# MicroController.net
KiCad netlist of a schematic drawn in Altium Designer
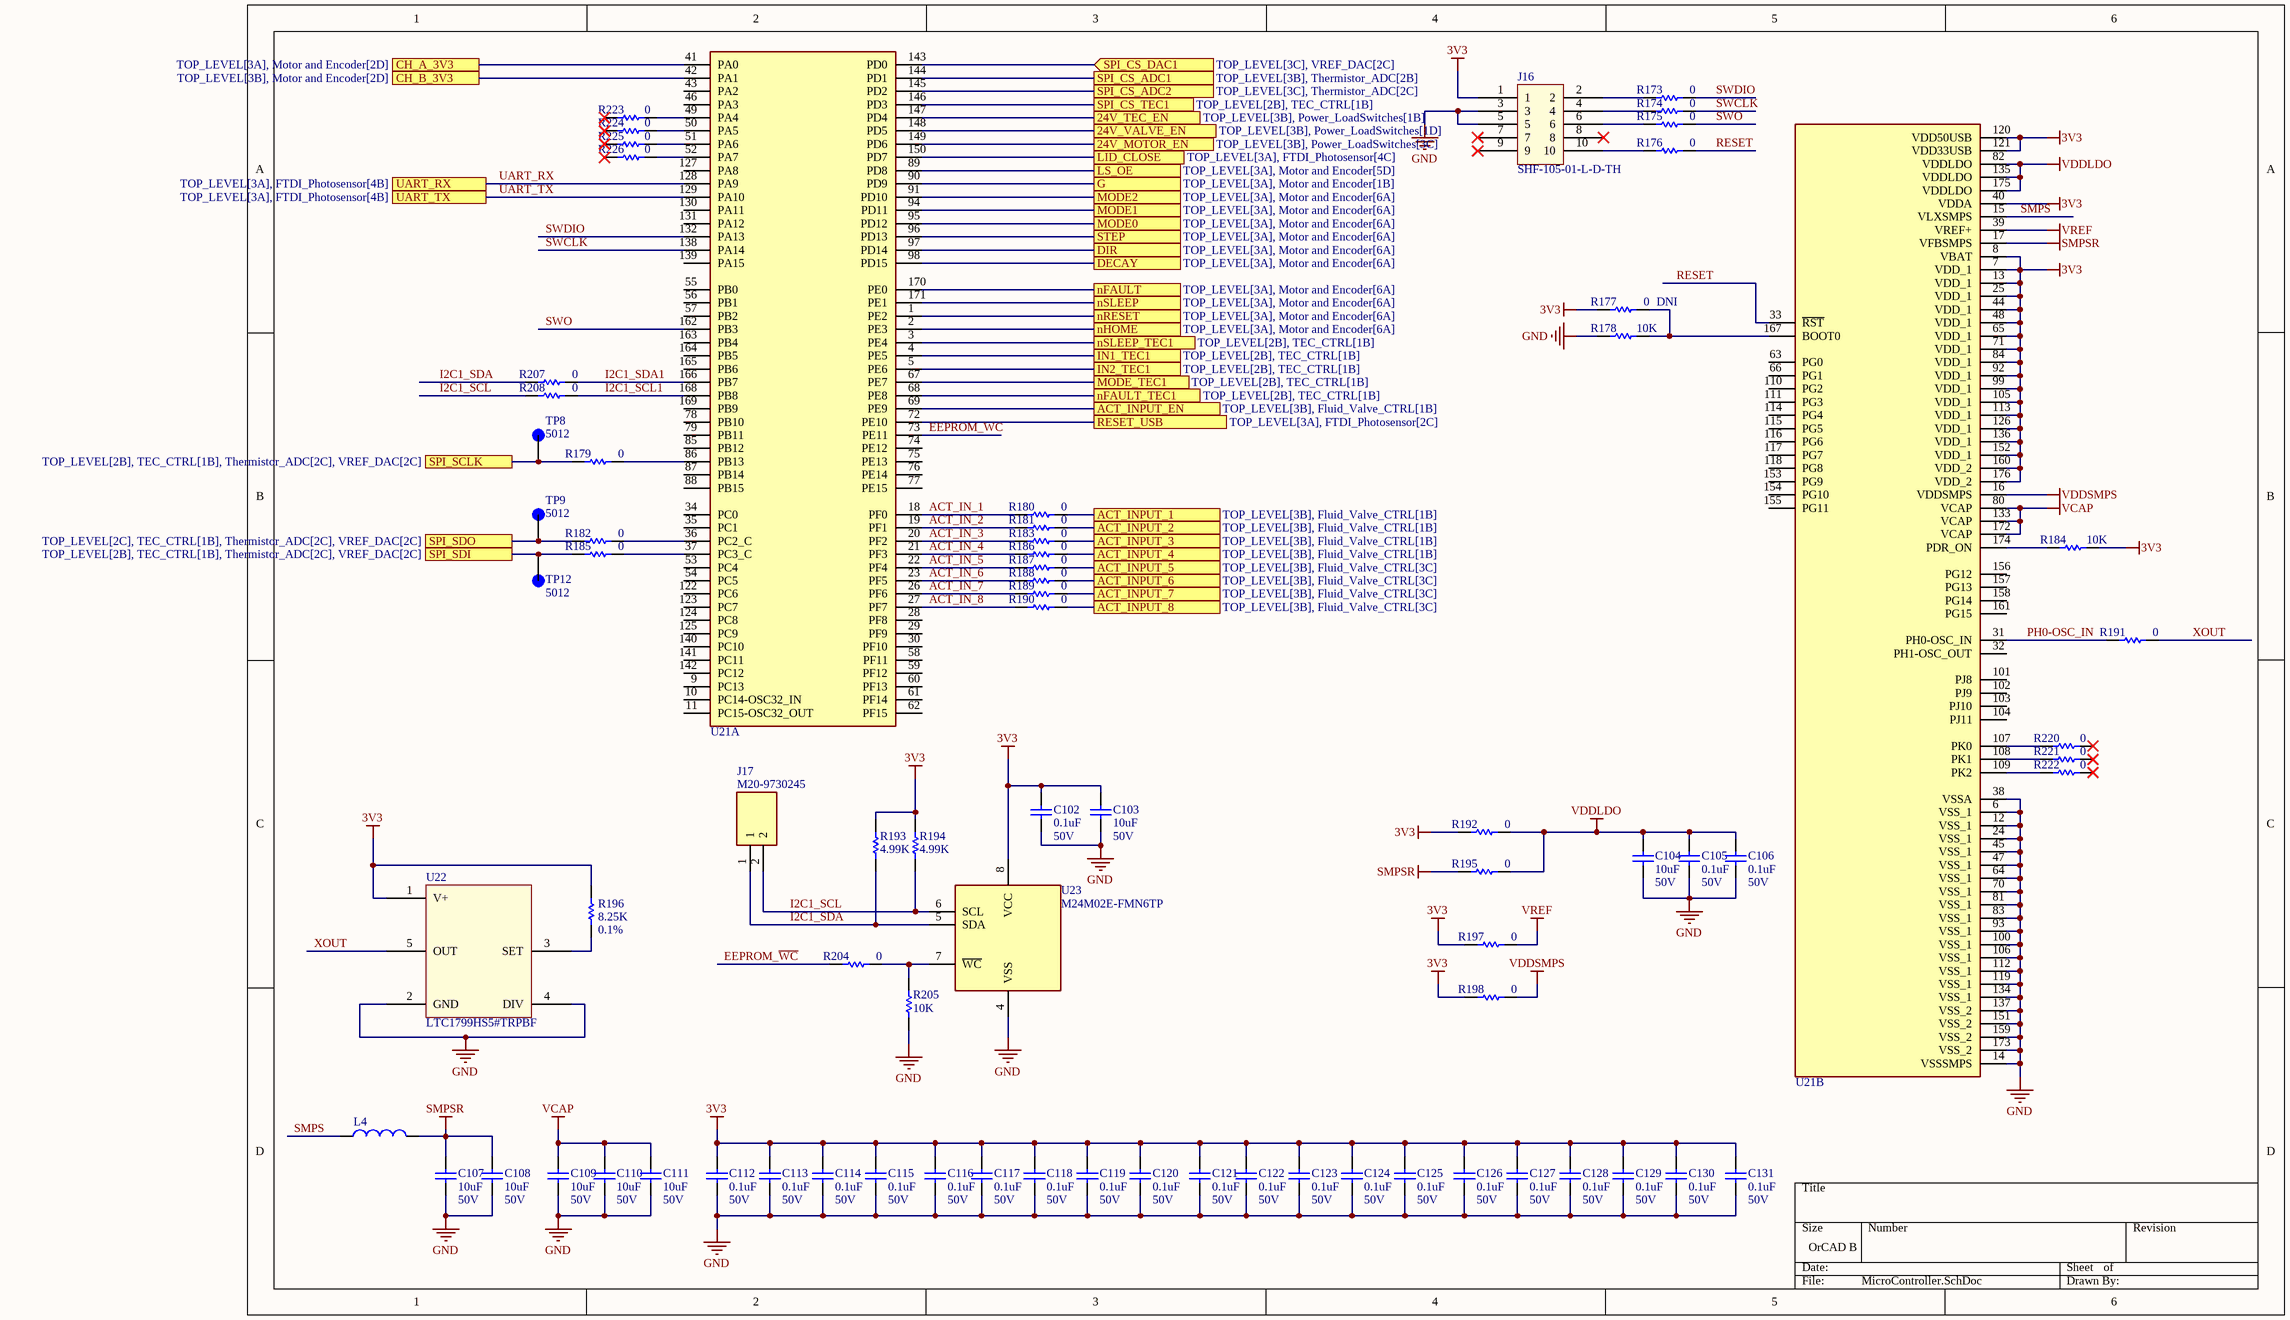
[diagram p0: MicroController.SchDoc]

(export (version "E")
  (design (tool "Eeschema 10.0.6"))
  (components
    (comp (ref "C102")
      (value "0.1uF")
      (footprint "DEFAULT_CAPACITOR_0805")
      (description "CAP CER 0.1UF 50V X7R 0805")
      (fields
        (field (name "MANUFACTURER") "Cal-Chip Electronics, Inc.")
        (field (name "RATING") "50V")
        (field (name "Comment") "KGM21NR71H104KT")
      )
      (libsource (lib "Avery Altium Llibrary") (part "KGM21NR71H104KT"))
    )
    (comp (ref "C103")
      (value "10uF")
      (footprint "DEFAULT_CAPACITOR_0805")
      (description "CAP CER 10UF 50V X5R 0805")
      (fields (field (name "RATING") "50V") (field (name "Comment") "GRM21BR61H106KE43L"))
      (libsource (lib "Avery Altium Llibrary") (part "GRM21BR61H106KE43L"))
    )
    (comp (ref "C104")
      (value "10uF")
      (footprint "DEFAULT_CAPACITOR_0805")
      (description "CAP CER 10UF 50V X5R 0805")
      (fields (field (name "RATING") "50V") (field (name "Comment") "GRM21BR61H106KE43L"))
      (libsource (lib "Avery Altium Llibrary") (part "GRM21BR61H106KE43L"))
    )
    (comp (ref "C105")
      (value "0.1uF")
      (footprint "DEFAULT_CAPACITOR_0805")
      (description "CAP CER 0.1UF 50V X7R 0805")
      (fields
        (field (name "MANUFACTURER") "Cal-Chip Electronics, Inc.")
        (field (name "RATING") "50V")
        (field (name "Comment") "KGM21NR71H104KT")
      )
      (libsource (lib "Avery Altium Llibrary") (part "KGM21NR71H104KT"))
    )
    (comp (ref "C106")
      (value "0.1uF")
      (footprint "DEFAULT_CAPACITOR_0805")
      (description "CAP CER 0.1UF 50V X7R 0805")
      (fields
        (field (name "MANUFACTURER") "Cal-Chip Electronics, Inc.")
        (field (name "RATING") "50V")
        (field (name "Comment") "KGM21NR71H104KT")
      )
      (libsource (lib "Avery Altium Llibrary") (part "KGM21NR71H104KT"))
    )
    (comp (ref "C107")
      (value "10uF")
      (footprint "DEFAULT_CAPACITOR_0805")
      (description "CAP CER 10UF 50V X5R 0805")
      (fields (field (name "RATING") "50V") (field (name "Comment") "GRM21BR61H106KE43L"))
      (libsource (lib "Avery Altium Llibrary") (part "GRM21BR61H106KE43L"))
    )
    (comp (ref "C108")
      (value "10uF")
      (footprint "DEFAULT_CAPACITOR_0805")
      (description "CAP CER 10UF 50V X5R 0805")
      (fields (field (name "RATING") "50V") (field (name "Comment") "GRM21BR61H106KE43L"))
      (libsource (lib "Avery Altium Llibrary") (part "GRM21BR61H106KE43L"))
    )
    (comp (ref "C109")
      (value "10uF")
      (footprint "DEFAULT_CAPACITOR_0805")
      (description "CAP CER 10UF 50V X5R 0805")
      (fields (field (name "RATING") "50V") (field (name "Comment") "GRM21BR61H106KE43L"))
      (libsource (lib "Avery Altium Llibrary") (part "GRM21BR61H106KE43L"))
    )
    (comp (ref "C110")
      (value "10uF")
      (footprint "DEFAULT_CAPACITOR_0805")
      (description "CAP CER 10UF 50V X5R 0805")
      (fields (field (name "RATING") "50V") (field (name "Comment") "GRM21BR61H106KE43L"))
      (libsource (lib "Avery Altium Llibrary") (part "GRM21BR61H106KE43L"))
    )
    (comp (ref "C111")
      (value "10uF")
      (footprint "DEFAULT_CAPACITOR_0805")
      (description "CAP CER 10UF 50V X5R 0805")
      (fields (field (name "RATING") "50V") (field (name "Comment") "GRM21BR61H106KE43L"))
      (libsource (lib "Avery Altium Llibrary") (part "GRM21BR61H106KE43L"))
    )
    (comp (ref "C112")
      (value "0.1uF")
      (footprint "DEFAULT_CAPACITOR_0805")
      (description "CAP CER 0.1UF 50V X7R 0805")
      (fields
        (field (name "MANUFACTURER") "Cal-Chip Electronics, Inc.")
        (field (name "RATING") "50V")
        (field (name "Comment") "KGM21NR71H104KT")
      )
      (libsource (lib "Avery Altium Llibrary") (part "KGM21NR71H104KT"))
    )
    (comp (ref "C113")
      (value "0.1uF")
      (footprint "DEFAULT_CAPACITOR_0805")
      (description "CAP CER 0.1UF 50V X7R 0805")
      (fields
        (field (name "MANUFACTURER") "Cal-Chip Electronics, Inc.")
        (field (name "RATING") "50V")
        (field (name "Comment") "KGM21NR71H104KT")
      )
      (libsource (lib "Avery Altium Llibrary") (part "KGM21NR71H104KT"))
    )
    (comp (ref "C114")
      (value "0.1uF")
      (footprint "DEFAULT_CAPACITOR_0805")
      (description "CAP CER 0.1UF 50V X7R 0805")
      (fields
        (field (name "MANUFACTURER") "Cal-Chip Electronics, Inc.")
        (field (name "RATING") "50V")
        (field (name "Comment") "KGM21NR71H104KT")
      )
      (libsource (lib "Avery Altium Llibrary") (part "KGM21NR71H104KT"))
    )
    (comp (ref "C115")
      (value "0.1uF")
      (footprint "DEFAULT_CAPACITOR_0805")
      (description "CAP CER 0.1UF 50V X7R 0805")
      (fields
        (field (name "MANUFACTURER") "Cal-Chip Electronics, Inc.")
        (field (name "RATING") "50V")
        (field (name "Comment") "KGM21NR71H104KT")
      )
      (libsource (lib "Avery Altium Llibrary") (part "KGM21NR71H104KT"))
    )
    (comp (ref "C116")
      (value "0.1uF")
      (footprint "DEFAULT_CAPACITOR_0805")
      (description "CAP CER 0.1UF 50V X7R 0805")
      (fields
        (field (name "MANUFACTURER") "Cal-Chip Electronics, Inc.")
        (field (name "RATING") "50V")
        (field (name "Comment") "KGM21NR71H104KT")
      )
      (libsource (lib "Avery Altium Llibrary") (part "KGM21NR71H104KT"))
    )
    (comp (ref "C117")
      (value "0.1uF")
      (footprint "DEFAULT_CAPACITOR_0805")
      (description "CAP CER 0.1UF 50V X7R 0805")
      (fields
        (field (name "MANUFACTURER") "Cal-Chip Electronics, Inc.")
        (field (name "RATING") "50V")
        (field (name "Comment") "KGM21NR71H104KT")
      )
      (libsource (lib "Avery Altium Llibrary") (part "KGM21NR71H104KT"))
    )
    (comp (ref "C118")
      (value "0.1uF")
      (footprint "DEFAULT_CAPACITOR_0805")
      (description "CAP CER 0.1UF 50V X7R 0805")
      (fields
        (field (name "MANUFACTURER") "Cal-Chip Electronics, Inc.")
        (field (name "RATING") "50V")
        (field (name "Comment") "KGM21NR71H104KT")
      )
      (libsource (lib "Avery Altium Llibrary") (part "KGM21NR71H104KT"))
    )
    (comp (ref "C119")
      (value "0.1uF")
      (footprint "DEFAULT_CAPACITOR_0805")
      (description "CAP CER 0.1UF 50V X7R 0805")
      (fields
        (field (name "MANUFACTURER") "Cal-Chip Electronics, Inc.")
        (field (name "RATING") "50V")
        (field (name "Comment") "KGM21NR71H104KT")
      )
      (libsource (lib "Avery Altium Llibrary") (part "KGM21NR71H104KT"))
    )
    (comp (ref "C120")
      (value "0.1uF")
      (footprint "DEFAULT_CAPACITOR_0805")
      (description "CAP CER 0.1UF 50V X7R 0805")
      (fields
        (field (name "MANUFACTURER") "Cal-Chip Electronics, Inc.")
        (field (name "RATING") "50V")
        (field (name "Comment") "KGM21NR71H104KT")
      )
      (libsource (lib "Avery Altium Llibrary") (part "KGM21NR71H104KT"))
    )
    (comp (ref "C121")
      (value "0.1uF")
      (footprint "DEFAULT_CAPACITOR_0805")
      (description "CAP CER 0.1UF 50V X7R 0805")
      (fields
        (field (name "MANUFACTURER") "Cal-Chip Electronics, Inc.")
        (field (name "RATING") "50V")
        (field (name "Comment") "KGM21NR71H104KT")
      )
      (libsource (lib "Avery Altium Llibrary") (part "KGM21NR71H104KT"))
    )
    (comp (ref "C122")
      (value "0.1uF")
      (footprint "DEFAULT_CAPACITOR_0805")
      (description "CAP CER 0.1UF 50V X7R 0805")
      (fields
        (field (name "MANUFACTURER") "Cal-Chip Electronics, Inc.")
        (field (name "RATING") "50V")
        (field (name "Comment") "KGM21NR71H104KT")
      )
      (libsource (lib "Avery Altium Llibrary") (part "KGM21NR71H104KT"))
    )
    (comp (ref "C123")
      (value "0.1uF")
      (footprint "DEFAULT_CAPACITOR_0805")
      (description "CAP CER 0.1UF 50V X7R 0805")
      (fields
        (field (name "MANUFACTURER") "Cal-Chip Electronics, Inc.")
        (field (name "RATING") "50V")
        (field (name "Comment") "KGM21NR71H104KT")
      )
      (libsource (lib "Avery Altium Llibrary") (part "KGM21NR71H104KT"))
    )
    (comp (ref "C124")
      (value "0.1uF")
      (footprint "DEFAULT_CAPACITOR_0805")
      (description "CAP CER 0.1UF 50V X7R 0805")
      (fields
        (field (name "MANUFACTURER") "Cal-Chip Electronics, Inc.")
        (field (name "RATING") "50V")
        (field (name "Comment") "KGM21NR71H104KT")
      )
      (libsource (lib "Avery Altium Llibrary") (part "KGM21NR71H104KT"))
    )
    (comp (ref "C125")
      (value "0.1uF")
      (footprint "DEFAULT_CAPACITOR_0805")
      (description "CAP CER 0.1UF 50V X7R 0805")
      (fields
        (field (name "MANUFACTURER") "Cal-Chip Electronics, Inc.")
        (field (name "RATING") "50V")
        (field (name "Comment") "KGM21NR71H104KT")
      )
      (libsource (lib "Avery Altium Llibrary") (part "KGM21NR71H104KT"))
    )
    (comp (ref "C126")
      (value "0.1uF")
      (footprint "DEFAULT_CAPACITOR_0805")
      (description "CAP CER 0.1UF 50V X7R 0805")
      (fields
        (field (name "MANUFACTURER") "Cal-Chip Electronics, Inc.")
        (field (name "RATING") "50V")
        (field (name "Comment") "KGM21NR71H104KT")
      )
      (libsource (lib "Avery Altium Llibrary") (part "KGM21NR71H104KT"))
    )
    (comp (ref "C127")
      (value "0.1uF")
      (footprint "DEFAULT_CAPACITOR_0805")
      (description "CAP CER 0.1UF 50V X7R 0805")
      (fields
        (field (name "MANUFACTURER") "Cal-Chip Electronics, Inc.")
        (field (name "RATING") "50V")
        (field (name "Comment") "KGM21NR71H104KT")
      )
      (libsource (lib "Avery Altium Llibrary") (part "KGM21NR71H104KT"))
    )
    (comp (ref "C128")
      (value "0.1uF")
      (footprint "DEFAULT_CAPACITOR_0805")
      (description "CAP CER 0.1UF 50V X7R 0805")
      (fields
        (field (name "MANUFACTURER") "Cal-Chip Electronics, Inc.")
        (field (name "RATING") "50V")
        (field (name "Comment") "KGM21NR71H104KT")
      )
      (libsource (lib "Avery Altium Llibrary") (part "KGM21NR71H104KT"))
    )
    (comp (ref "C129")
      (value "0.1uF")
      (footprint "DEFAULT_CAPACITOR_0805")
      (description "CAP CER 0.1UF 50V X7R 0805")
      (fields
        (field (name "MANUFACTURER") "Cal-Chip Electronics, Inc.")
        (field (name "RATING") "50V")
        (field (name "Comment") "KGM21NR71H104KT")
      )
      (libsource (lib "Avery Altium Llibrary") (part "KGM21NR71H104KT"))
    )
    (comp (ref "C130")
      (value "0.1uF")
      (footprint "DEFAULT_CAPACITOR_0805")
      (description "CAP CER 0.1UF 50V X7R 0805")
      (fields
        (field (name "MANUFACTURER") "Cal-Chip Electronics, Inc.")
        (field (name "RATING") "50V")
        (field (name "Comment") "KGM21NR71H104KT")
      )
      (libsource (lib "Avery Altium Llibrary") (part "KGM21NR71H104KT"))
    )
    (comp (ref "C131")
      (value "0.1uF")
      (footprint "DEFAULT_CAPACITOR_0805")
      (description "CAP CER 0.1UF 50V X7R 0805")
      (fields
        (field (name "MANUFACTURER") "Cal-Chip Electronics, Inc.")
        (field (name "RATING") "50V")
        (field (name "Comment") "KGM21NR71H104KT")
      )
      (libsource (lib "Avery Altium Llibrary") (part "KGM21NR71H104KT"))
    )
    (comp (ref "J16")
      (value "SHF-105-01-L-D-TH")
      (footprint "SAMTEC-SHF-105-01-L-D-TH")
      (description "CONN HEADER VERT 10POS 1.27MM")
      (fields (field (name "MANUFACTURER") "Sametc") (field (name "MANUFACTURER P/N") "SHF-105-01-L-D-TH"))
      (libsource (lib "Avery Altium Llibrary") (part "SHF-105-01-L-D-TH"))
    )
    (comp (ref "J17")
      (value "M20-9730245")
      (footprint "M209730245")
      (description "M20: 2 Pos Plug SIL Straight 3mm THT Connector 7mm pin Gold")
      (fields (field (name "MOUSER PART NUMBER") "855-M20-9730245"))
      (libsource (lib "Avery Altium Llibrary") (part "M20-9730245"))
    )
    (comp (ref "L4")
      (value "LQM2MPN2R2MG0L")
      (footprint "INDC2016X100N")
      (description "Inductor with Inductance: 2.2uH Tol. +/-20%, Package: 0806 (2016)")
      (libsource (lib "Avery Altium Llibrary") (part "LQM2MPN2R2MG0L"))
    )
    (comp (ref "R173")
      (value "0")
      (footprint "DEFAULT_RESISTOR_0805")
      (description "RES 0 OHM JUMPER 1/8W 0805")
      (fields (field (name "POWER") "1/8W") (field (name "Comment") "RC0805JR-070RL"))
      (libsource (lib "Avery Altium Llibrary") (part "RC0805JR-070RL"))
    )
    (comp (ref "R174")
      (value "0")
      (footprint "DEFAULT_RESISTOR_0805")
      (description "RES 0 OHM JUMPER 1/8W 0805")
      (fields (field (name "POWER") "1/8W") (field (name "Comment") "RC0805JR-070RL"))
      (libsource (lib "Avery Altium Llibrary") (part "RC0805JR-070RL"))
    )
    (comp (ref "R175")
      (value "0")
      (footprint "DEFAULT_RESISTOR_0805")
      (description "RES 0 OHM JUMPER 1/8W 0805")
      (fields (field (name "POWER") "1/8W") (field (name "Comment") "RC0805JR-070RL"))
      (libsource (lib "Avery Altium Llibrary") (part "RC0805JR-070RL"))
    )
    (comp (ref "R176")
      (value "0")
      (footprint "DEFAULT_RESISTOR_0805")
      (description "RES 0 OHM JUMPER 1/8W 0805")
      (fields (field (name "POWER") "1/8W") (field (name "Comment") "RC0805JR-070RL"))
      (libsource (lib "Avery Altium Llibrary") (part "RC0805JR-070RL"))
    )
    (comp (ref "R177")
      (value "DNI")
      (footprint "DEFAULT_RESISTOR_0805")
      (description "RES 0 OHM JUMPER 1/8W 0805")
      (fields (field (name "POWER") "1/8W") (field (name "ALTIUM_VALUE") "0"))
      (libsource (lib "Avery Altium Llibrary") (part "RC0805JR-070RL"))
    )
    (comp (ref "R178")
      (value "10K")
      (footprint "DEFAULT_RESISTOR_0805")
      (description "RES SMD 10K OHM 1% 1/4W 0805")
      (fields (field (name "POWER") "1/4W") (field (name "TOLERANCE") "1%"))
      (libsource (lib "Avery Altium Llibrary") (part "CRCW080510K0FKEA"))
    )
    (comp (ref "R179")
      (value "0")
      (footprint "DEFAULT_RESISTOR_0805")
      (description "RES 0 OHM JUMPER 1/8W 0805")
      (fields (field (name "POWER") "1/8W") (field (name "Comment") "RC0805JR-070RL"))
      (libsource (lib "Avery Altium Llibrary") (part "RC0805JR-070RL"))
    )
    (comp (ref "R180")
      (value "0")
      (footprint "DEFAULT_RESISTOR_0805")
      (description "RES 0 OHM JUMPER 1/8W 0805")
      (fields (field (name "POWER") "1/8W") (field (name "Comment") "RC0805JR-070RL"))
      (libsource (lib "Avery Altium Llibrary") (part "RC0805JR-070RL"))
    )
    (comp (ref "R181")
      (value "0")
      (footprint "DEFAULT_RESISTOR_0805")
      (description "RES 0 OHM JUMPER 1/8W 0805")
      (fields (field (name "POWER") "1/8W") (field (name "Comment") "RC0805JR-070RL"))
      (libsource (lib "Avery Altium Llibrary") (part "RC0805JR-070RL"))
    )
    (comp (ref "R182")
      (value "0")
      (footprint "DEFAULT_RESISTOR_0805")
      (description "RES 0 OHM JUMPER 1/8W 0805")
      (fields (field (name "POWER") "1/8W") (field (name "Comment") "RC0805JR-070RL"))
      (libsource (lib "Avery Altium Llibrary") (part "RC0805JR-070RL"))
    )
    (comp (ref "R183")
      (value "0")
      (footprint "DEFAULT_RESISTOR_0805")
      (description "RES 0 OHM JUMPER 1/8W 0805")
      (fields (field (name "POWER") "1/8W") (field (name "Comment") "RC0805JR-070RL"))
      (libsource (lib "Avery Altium Llibrary") (part "RC0805JR-070RL"))
    )
    (comp (ref "R184")
      (value "10K")
      (footprint "DEFAULT_RESISTOR_0805")
      (description "RES SMD 10K OHM 1% 1/4W 0805")
      (fields (field (name "POWER") "1/4W") (field (name "TOLERANCE") "1%"))
      (libsource (lib "Avery Altium Llibrary") (part "CRCW080510K0FKEA"))
    )
    (comp (ref "R185")
      (value "0")
      (footprint "DEFAULT_RESISTOR_0805")
      (description "RES 0 OHM JUMPER 1/8W 0805")
      (fields (field (name "POWER") "1/8W") (field (name "Comment") "RC0805JR-070RL"))
      (libsource (lib "Avery Altium Llibrary") (part "RC0805JR-070RL"))
    )
    (comp (ref "R186")
      (value "0")
      (footprint "DEFAULT_RESISTOR_0805")
      (description "RES 0 OHM JUMPER 1/8W 0805")
      (fields (field (name "POWER") "1/8W") (field (name "Comment") "RC0805JR-070RL"))
      (libsource (lib "Avery Altium Llibrary") (part "RC0805JR-070RL"))
    )
    (comp (ref "R187")
      (value "0")
      (footprint "DEFAULT_RESISTOR_0805")
      (description "RES 0 OHM JUMPER 1/8W 0805")
      (fields (field (name "POWER") "1/8W") (field (name "Comment") "RC0805JR-070RL"))
      (libsource (lib "Avery Altium Llibrary") (part "RC0805JR-070RL"))
    )
    (comp (ref "R188")
      (value "0")
      (footprint "DEFAULT_RESISTOR_0805")
      (description "RES 0 OHM JUMPER 1/8W 0805")
      (fields (field (name "POWER") "1/8W") (field (name "Comment") "RC0805JR-070RL"))
      (libsource (lib "Avery Altium Llibrary") (part "RC0805JR-070RL"))
    )
    (comp (ref "R189")
      (value "0")
      (footprint "DEFAULT_RESISTOR_0805")
      (description "RES 0 OHM JUMPER 1/8W 0805")
      (fields (field (name "POWER") "1/8W") (field (name "Comment") "RC0805JR-070RL"))
      (libsource (lib "Avery Altium Llibrary") (part "RC0805JR-070RL"))
    )
    (comp (ref "R190")
      (value "0")
      (footprint "DEFAULT_RESISTOR_0805")
      (description "RES 0 OHM JUMPER 1/8W 0805")
      (fields (field (name "POWER") "1/8W") (field (name "Comment") "RC0805JR-070RL"))
      (libsource (lib "Avery Altium Llibrary") (part "RC0805JR-070RL"))
    )
    (comp (ref "R191")
      (value "0")
      (footprint "DEFAULT_RESISTOR_0805")
      (description "RES 0 OHM JUMPER 1/8W 0805")
      (fields (field (name "POWER") "1/8W") (field (name "Comment") "RC0805JR-070RL"))
      (libsource (lib "Avery Altium Llibrary") (part "RC0805JR-070RL"))
    )
    (comp (ref "R192")
      (value "0")
      (footprint "DEFAULT_RESISTOR_0805")
      (description "RES 0 OHM JUMPER 1/8W 0805")
      (fields (field (name "POWER") "1/8W") (field (name "Comment") "RC0805JR-070RL"))
      (libsource (lib "Avery Altium Llibrary") (part "RC0805JR-070RL"))
    )
    (comp (ref "R193")
      (value "4.99K")
      (footprint "DEFAULT_RESISTOR_0805")
      (description "RES 4.99K OHM 1% 1/8W 0805")
      (fields (field (name "POWER") "1/8W") (field (name "TOLERANCE") "1%"))
      (libsource (lib "Avery Altium Llibrary") (part "RMCF0805FT4K99"))
    )
    (comp (ref "R194")
      (value "4.99K")
      (footprint "DEFAULT_RESISTOR_0805")
      (description "RES 4.99K OHM 1% 1/8W 0805")
      (fields (field (name "POWER") "1/8W") (field (name "TOLERANCE") "1%"))
      (libsource (lib "Avery Altium Llibrary") (part "RMCF0805FT4K99"))
    )
    (comp (ref "R195")
      (value "0")
      (footprint "DEFAULT_RESISTOR_0805")
      (description "RES 0 OHM JUMPER 1/8W 0805")
      (fields (field (name "POWER") "1/8W") (field (name "Comment") "RC0805JR-070RL"))
      (libsource (lib "Avery Altium Llibrary") (part "RC0805JR-070RL"))
    )
    (comp (ref "R196")
      (value "8.25K")
      (footprint "DEFAULT_RESISTOR_0805")
      (description "RES SMD 8.25K OHM 0.1% 1/8W 0805")
      (fields
        (field (name "POWER") "1/8W")
        (field (name "TOLERANCE") "0.1%")
        (field (name "Comment") "ERA-6AEB8251V")
      )
      (libsource (lib "Avery Altium Llibrary") (part "ERA-6AEB8251V"))
    )
    (comp (ref "R197")
      (value "0")
      (footprint "DEFAULT_RESISTOR_0805")
      (description "RES 0 OHM JUMPER 1/8W 0805")
      (fields (field (name "POWER") "1/8W") (field (name "Comment") "RC0805JR-070RL"))
      (libsource (lib "Avery Altium Llibrary") (part "RC0805JR-070RL"))
    )
    (comp (ref "R198")
      (value "0")
      (footprint "DEFAULT_RESISTOR_0805")
      (description "RES 0 OHM JUMPER 1/8W 0805")
      (fields (field (name "POWER") "1/8W") (field (name "Comment") "RC0805JR-070RL"))
      (libsource (lib "Avery Altium Llibrary") (part "RC0805JR-070RL"))
    )
    (comp (ref "R204")
      (value "0")
      (footprint "DEFAULT_RESISTOR_0805")
      (description "RES 0 OHM JUMPER 1/8W 0805")
      (fields (field (name "POWER") "1/8W") (field (name "Comment") "RC0805JR-070RL"))
      (libsource (lib "Avery Altium Llibrary") (part "RC0805JR-070RL"))
    )
    (comp (ref "R205")
      (value "10K")
      (footprint "DEFAULT_RESISTOR_0805")
      (description "RES SMD 10K OHM 1% 1/4W 0805")
      (fields (field (name "POWER") "1/4W") (field (name "TOLERANCE") "1%"))
      (libsource (lib "Avery Altium Llibrary") (part "CRCW080510K0FKEA"))
    )
    (comp (ref "R207")
      (value "0")
      (footprint "DEFAULT_RESISTOR_0805")
      (description "RES 0 OHM JUMPER 1/8W 0805")
      (fields (field (name "POWER") "1/8W") (field (name "Comment") "RC0805JR-070RL"))
      (libsource (lib "Avery Altium Llibrary") (part "RC0805JR-070RL"))
    )
    (comp (ref "R208")
      (value "0")
      (footprint "DEFAULT_RESISTOR_0805")
      (description "RES 0 OHM JUMPER 1/8W 0805")
      (fields (field (name "POWER") "1/8W") (field (name "Comment") "RC0805JR-070RL"))
      (libsource (lib "Avery Altium Llibrary") (part "RC0805JR-070RL"))
    )
    (comp (ref "R220")
      (value "0")
      (footprint "DEFAULT_RESISTOR_0805")
      (description "RES 0 OHM JUMPER 1/8W 0805")
      (fields (field (name "POWER") "1/8W") (field (name "Comment") "RC0805JR-070RL"))
      (libsource (lib "Avery Altium Llibrary") (part "RC0805JR-070RL"))
    )
    (comp (ref "R221")
      (value "0")
      (footprint "DEFAULT_RESISTOR_0805")
      (description "RES 0 OHM JUMPER 1/8W 0805")
      (fields (field (name "POWER") "1/8W") (field (name "Comment") "RC0805JR-070RL"))
      (libsource (lib "Avery Altium Llibrary") (part "RC0805JR-070RL"))
    )
    (comp (ref "R222")
      (value "0")
      (footprint "DEFAULT_RESISTOR_0805")
      (description "RES 0 OHM JUMPER 1/8W 0805")
      (fields (field (name "POWER") "1/8W") (field (name "Comment") "RC0805JR-070RL"))
      (libsource (lib "Avery Altium Llibrary") (part "RC0805JR-070RL"))
    )
    (comp (ref "R223")
      (value "0")
      (footprint "DEFAULT_RESISTOR_0805")
      (description "RES 0 OHM JUMPER 1/8W 0805")
      (fields (field (name "POWER") "1/8W") (field (name "Comment") "RC0805JR-070RL"))
      (libsource (lib "Avery Altium Llibrary") (part "RC0805JR-070RL"))
    )
    (comp (ref "R224")
      (value "0")
      (footprint "DEFAULT_RESISTOR_0805")
      (description "RES 0 OHM JUMPER 1/8W 0805")
      (fields (field (name "POWER") "1/8W") (field (name "Comment") "RC0805JR-070RL"))
      (libsource (lib "Avery Altium Llibrary") (part "RC0805JR-070RL"))
    )
    (comp (ref "R225")
      (value "0")
      (footprint "DEFAULT_RESISTOR_0805")
      (description "RES 0 OHM JUMPER 1/8W 0805")
      (fields (field (name "POWER") "1/8W") (field (name "Comment") "RC0805JR-070RL"))
      (libsource (lib "Avery Altium Llibrary") (part "RC0805JR-070RL"))
    )
    (comp (ref "R226")
      (value "0")
      (footprint "DEFAULT_RESISTOR_0805")
      (description "RES 0 OHM JUMPER 1/8W 0805")
      (fields (field (name "POWER") "1/8W") (field (name "Comment") "RC0805JR-070RL"))
      (libsource (lib "Avery Altium Llibrary") (part "RC0805JR-070RL"))
    )
    (comp (ref "TP8")
      (value "5012")
      (footprint "TP_5011")
      (description "PC TEST POINT MULTIPURPOSE WHITE")
      (libsource (lib "Avery Altium Llibrary") (part "5012"))
    )
    (comp (ref "TP9")
      (value "5012")
      (footprint "TP_5011")
      (description "PC TEST POINT MULTIPURPOSE WHITE")
      (libsource (lib "Avery Altium Llibrary") (part "5012"))
    )
    (comp (ref "TP12")
      (value "5012")
      (footprint "TP_5011")
      (description "PC TEST POINT MULTIPURPOSE WHITE")
      (libsource (lib "Avery Altium Llibrary") (part "5012"))
    )
    (comp (ref "U21")
      (value "STM32H735IGT6")
      (footprint "STM32H7351GT6-LQFP176")
      (description "ARM® Cortex®-M7 STM32H7 Microcontroller IC 32-Bit 550MHz 1MB (1M x 8) FLASH 176-LQFP (24x24)")
      (fields (field (name "MANUFACTURER") "STMicroelectronics"))
      (libsource (lib "Avery Schem Library") (part "STM32H735IGT6"))
    )
    (comp (ref "U22")
      (value "LTC1799HS5#TRPBF")
      (footprint "LTC1799HS5-TSOT23-5")
      (description "IC OSC SILICON PROG TSOT23-5")
      (fields
        (field (name "MANUFACTURER") "Analog Devices")
        (field (name "MANUFACTURER P/N") "LTC1799HS5#TRPBF")
      )
      (libsource (lib "Avery Schem Library") (part "LTC1799HS5#TRPBF"))
    )
    (comp (ref "U23")
      (value "M24M02E-FMN6TP")
      (footprint "8ld - SOIC")
      (description "EEPROM Memory IC 2Mbit I2C 1 MHz 450 ns 8-SO")
      (fields (field (name "MP") "M24M02E-FMN") (field (name "DESIGNER") "OMIGA"))
      (libsource (lib "Avery Schem Library") (part "M24M02E-FMN6TP"))
    )
  )
  (nets
    (net (code "1") (name "/24V_MOTOR_EN") (class "Default")
      (node (ref "U21") (pin "149") (pinfunction "PD6_149") (pintype "passive"))
    )
    (net (code "2") (name "/24V_TEC_EN") (class "Default")
      (node (ref "U21") (pin "147") (pinfunction "PD4_147") (pintype "passive"))
    )
    (net (code "3") (name "/24V_VALVE_EN") (class "Default")
      (node (ref "U21") (pin "148") (pinfunction "PD5_148") (pintype "passive"))
    )
    (net (code "4") (name "/ACT_INPUT_1") (class "Default")
      (node (ref "R180") (pin "1") (pinfunction "1_1") (pintype "passive"))
    )
    (net (code "5") (name "/ACT_INPUT_2") (class "Default")
      (node (ref "R181") (pin "1") (pinfunction "1_1") (pintype "passive"))
    )
    (net (code "6") (name "/ACT_INPUT_3") (class "Default")
      (node (ref "R183") (pin "1") (pinfunction "1_1") (pintype "passive"))
    )
    (net (code "7") (name "/ACT_INPUT_4") (class "Default")
      (node (ref "R186") (pin "1") (pinfunction "1_1") (pintype "passive"))
    )
    (net (code "8") (name "/ACT_INPUT_5") (class "Default")
      (node (ref "R187") (pin "1") (pinfunction "1_1") (pintype "passive"))
    )
    (net (code "9") (name "/ACT_INPUT_6") (class "Default")
      (node (ref "R188") (pin "1") (pinfunction "1_1") (pintype "passive"))
    )
    (net (code "10") (name "/ACT_INPUT_7") (class "Default")
      (node (ref "R189") (pin "1") (pinfunction "1_1") (pintype "passive"))
    )
    (net (code "11") (name "/ACT_INPUT_8") (class "Default")
      (node (ref "R190") (pin "1") (pinfunction "1_1") (pintype "passive"))
    )
    (net (code "12") (name "/ACT_INPUT_EN") (class "Default")
      (node (ref "U21") (pin "69") (pinfunction "PE9_69") (pintype "passive"))
    )
    (net (code "13") (name "/ACT_IN_1") (class "Default")
      (node (ref "R180") (pin "2") (pinfunction "2_2") (pintype "passive"))
      (node (ref "U21") (pin "18") (pinfunction "PF0_18") (pintype "passive"))
    )
    (net (code "14") (name "/ACT_IN_2") (class "Default")
      (node (ref "R181") (pin "2") (pinfunction "2_2") (pintype "passive"))
      (node (ref "U21") (pin "19") (pinfunction "PF1_19") (pintype "passive"))
    )
    (net (code "15") (name "/ACT_IN_3") (class "Default")
      (node (ref "R183") (pin "2") (pinfunction "2_2") (pintype "passive"))
      (node (ref "U21") (pin "20") (pinfunction "PF2_20") (pintype "passive"))
    )
    (net (code "16") (name "/ACT_IN_4") (class "Default")
      (node (ref "R186") (pin "2") (pinfunction "2_2") (pintype "passive"))
      (node (ref "U21") (pin "21") (pinfunction "PF3_21") (pintype "passive"))
    )
    (net (code "17") (name "/ACT_IN_5") (class "Default")
      (node (ref "R187") (pin "2") (pinfunction "2_2") (pintype "passive"))
      (node (ref "U21") (pin "22") (pinfunction "PF4_22") (pintype "passive"))
    )
    (net (code "18") (name "/ACT_IN_6") (class "Default")
      (node (ref "R188") (pin "2") (pinfunction "2_2") (pintype "passive"))
      (node (ref "U21") (pin "23") (pinfunction "PF5_23") (pintype "passive"))
    )
    (net (code "19") (name "/ACT_IN_7") (class "Default")
      (node (ref "R189") (pin "2") (pinfunction "2_2") (pintype "passive"))
      (node (ref "U21") (pin "26") (pinfunction "PF6_26") (pintype "passive"))
    )
    (net (code "20") (name "/ACT_IN_8") (class "Default")
      (node (ref "R190") (pin "2") (pinfunction "2_2") (pintype "passive"))
      (node (ref "U21") (pin "27") (pinfunction "PF7_27") (pintype "passive"))
    )
    (net (code "21") (name "/CH_A_3V3") (class "Default")
      (node (ref "U21") (pin "41") (pinfunction "PA0_41") (pintype "passive"))
    )
    (net (code "22") (name "/CH_B_3V3") (class "Default")
      (node (ref "U21") (pin "42") (pinfunction "PA1_42") (pintype "passive"))
    )
    (net (code "23") (name "/DECAY") (class "Default")
      (node (ref "U21") (pin "98") (pinfunction "PD15_98") (pintype "passive"))
    )
    (net (code "24") (name "/DIR") (class "Default")
      (node (ref "U21") (pin "97") (pinfunction "PD14_97") (pintype "passive"))
    )
    (net (code "25") (name "/EEPROM_~{WC}") (class "Default")
      (node (ref "R204") (pin "2") (pinfunction "2_2") (pintype "passive"))
      (node (ref "U21") (pin "73") (pinfunction "PE11_73") (pintype "passive"))
    )
    (net (code "26") (name "/G") (class "Default")
      (node (ref "U21") (pin "90") (pinfunction "PD9_90") (pintype "passive"))
    )
    (net (code "27") (name "/I2C1_SCL") (class "Default")
      (node (ref "J17") (pin "2") (pinfunction "2_2") (pintype "passive"))
      (node (ref "R194") (pin "2") (pinfunction "2_2") (pintype "passive"))
      (node (ref "R208") (pin "2") (pinfunction "2_2") (pintype "passive"))
      (node (ref "U23") (pin "6") (pinfunction "SCL_6") (pintype "passive"))
    )
    (net (code "28") (name "/I2C1_SCL1") (class "Default")
      (node (ref "R208") (pin "1") (pinfunction "1_1") (pintype "passive"))
      (node (ref "U21") (pin "168") (pinfunction "PB8_168") (pintype "passive"))
    )
    (net (code "29") (name "/I2C1_SDA") (class "Default")
      (node (ref "J17") (pin "1") (pinfunction "1_1") (pintype "passive"))
      (node (ref "R193") (pin "2") (pinfunction "2_2") (pintype "passive"))
      (node (ref "R207") (pin "2") (pinfunction "2_2") (pintype "passive"))
      (node (ref "U23") (pin "5") (pinfunction "SDA_5") (pintype "passive"))
    )
    (net (code "30") (name "/I2C1_SDA1") (class "Default")
      (node (ref "R207") (pin "1") (pinfunction "1_1") (pintype "passive"))
      (node (ref "U21") (pin "166") (pinfunction "PB7_166") (pintype "passive"))
    )
    (net (code "31") (name "/IN1_TEC1") (class "Default")
      (node (ref "U21") (pin "4") (pinfunction "PE5_4") (pintype "passive"))
    )
    (net (code "32") (name "/IN2_TEC1") (class "Default")
      (node (ref "U21") (pin "5") (pinfunction "PE6_5") (pintype "passive"))
    )
    (net (code "33") (name "/LID_CLOSE") (class "Default")
      (node (ref "U21") (pin "150") (pinfunction "PD7_150") (pintype "passive"))
    )
    (net (code "34") (name "/LS_OE") (class "Default")
      (node (ref "U21") (pin "89") (pinfunction "PD8_89") (pintype "passive"))
    )
    (net (code "35") (name "/MODE0") (class "Default")
      (node (ref "U21") (pin "95") (pinfunction "PD12_95") (pintype "passive"))
    )
    (net (code "36") (name "/MODE1") (class "Default")
      (node (ref "U21") (pin "94") (pinfunction "PD11_94") (pintype "passive"))
    )
    (net (code "37") (name "/MODE2") (class "Default")
      (node (ref "U21") (pin "91") (pinfunction "PD10_91") (pintype "passive"))
    )
    (net (code "38") (name "/MODE_TEC1") (class "Default")
      (node (ref "U21") (pin "67") (pinfunction "PE7_67") (pintype "passive"))
    )
    (net (code "39") (name "/PH0-OSC_IN") (class "Default")
      (node (ref "R191") (pin "2") (pinfunction "2_2") (pintype "passive"))
      (node (ref "U21") (pin "31") (pinfunction "PH0-OSC_IN_31") (pintype "passive"))
    )
    (net (code "40") (name "/RESET") (class "Default")
      (node (ref "R176") (pin "1") (pinfunction "1_1") (pintype "passive"))
      (node (ref "U21") (pin "33") (pinfunction "~{RST}_33") (pintype "passive"))
    )
    (net (code "41") (name "/RESET_USB") (class "Default")
      (node (ref "U21") (pin "72") (pinfunction "PE10_72") (pintype "passive"))
    )
    (net (code "42") (name "/SMPS") (class "Default")
      (node (ref "L4") (pin "1") (pinfunction "1_1") (pintype "passive"))
      (node (ref "U21") (pin "15") (pinfunction "VLXSMPS_15") (pintype "passive"))
    )
    (net (code "43") (name "/SPI_CS_ADC1") (class "Default")
      (node (ref "U21") (pin "144") (pinfunction "PD1_144") (pintype "passive"))
    )
    (net (code "44") (name "/SPI_CS_ADC2") (class "Default")
      (node (ref "U21") (pin "145") (pinfunction "PD2_145") (pintype "passive"))
    )
    (net (code "45") (name "/SPI_CS_DAC1") (class "Default")
      (node (ref "U21") (pin "143") (pinfunction "PD0_143") (pintype "passive"))
    )
    (net (code "46") (name "/SPI_CS_TEC1") (class "Default")
      (node (ref "U21") (pin "146") (pinfunction "PD3_146") (pintype "passive"))
    )
    (net (code "47") (name "/SPI_SCLK") (class "Default")
      (node (ref "R179") (pin "2") (pinfunction "2_2") (pintype "passive"))
      (node (ref "TP8") (pin "TP") (pinfunction "TP_TP") (pintype "passive"))
    )
    (net (code "48") (name "/SPI_SDI") (class "Default")
      (node (ref "R185") (pin "2") (pinfunction "2_2") (pintype "passive"))
      (node (ref "TP12") (pin "TP") (pinfunction "TP_TP") (pintype "passive"))
    )
    (net (code "49") (name "/SPI_SDO") (class "Default")
      (node (ref "R182") (pin "2") (pinfunction "2_2") (pintype "passive"))
      (node (ref "TP9") (pin "TP") (pinfunction "TP_TP") (pintype "passive"))
    )
    (net (code "50") (name "/STEP") (class "Default")
      (node (ref "U21") (pin "96") (pinfunction "PD13_96") (pintype "passive"))
    )
    (net (code "51") (name "/SWCLK") (class "Default")
      (node (ref "R174") (pin "1") (pinfunction "1_1") (pintype "passive"))
      (node (ref "U21") (pin "138") (pinfunction "PA14_138") (pintype "passive"))
    )
    (net (code "52") (name "/SWDIO") (class "Default")
      (node (ref "R173") (pin "1") (pinfunction "1_1") (pintype "passive"))
      (node (ref "U21") (pin "132") (pinfunction "PA13_132") (pintype "passive"))
    )
    (net (code "53") (name "/SWO") (class "Default")
      (node (ref "R175") (pin "1") (pinfunction "1_1") (pintype "passive"))
      (node (ref "U21") (pin "162") (pinfunction "PB3_162") (pintype "passive"))
    )
    (net (code "54") (name "/UART_RX") (class "Default")
      (node (ref "U21") (pin "128") (pinfunction "PA9_128") (pintype "passive"))
    )
    (net (code "55") (name "/UART_TX") (class "Default")
      (node (ref "U21") (pin "129") (pinfunction "PA10_129") (pintype "passive"))
    )
    (net (code "56") (name "/XOUT") (class "Default")
      (node (ref "R191") (pin "1") (pinfunction "1_1") (pintype "passive"))
      (node (ref "U22") (pin "5") (pinfunction "OUT_5") (pintype "passive"))
    )
    (net (code "57") (name "/nFAULT") (class "Default")
      (node (ref "U21") (pin "170") (pinfunction "PE0_170") (pintype "passive"))
    )
    (net (code "58") (name "/nFAULT_TEC1") (class "Default")
      (node (ref "U21") (pin "68") (pinfunction "PE8_68") (pintype "passive"))
    )
    (net (code "59") (name "/nHOME") (class "Default")
      (node (ref "U21") (pin "2") (pinfunction "PE3_2") (pintype "passive"))
    )
    (net (code "60") (name "/nRESET") (class "Default")
      (node (ref "U21") (pin "1") (pinfunction "PE2_1") (pintype "passive"))
    )
    (net (code "61") (name "/nSLEEP") (class "Default")
      (node (ref "U21") (pin "171") (pinfunction "PE1_171") (pintype "passive"))
    )
    (net (code "62") (name "/nSLEEP_TEC1") (class "Default")
      (node (ref "U21") (pin "3") (pinfunction "PE4_3") (pintype "passive"))
    )
    (net (code "63") (name "3V3") (class "Default")
      (node (ref "C102") (pin "2") (pinfunction "2_2") (pintype "passive"))
      (node (ref "C103") (pin "2") (pinfunction "2_2") (pintype "passive"))
      (node (ref "C112") (pin "2") (pinfunction "2_2") (pintype "passive"))
      (node (ref "C113") (pin "2") (pinfunction "2_2") (pintype "passive"))
      (node (ref "C114") (pin "2") (pinfunction "2_2") (pintype "passive"))
      (node (ref "C115") (pin "2") (pinfunction "2_2") (pintype "passive"))
      (node (ref "C116") (pin "2") (pinfunction "2_2") (pintype "passive"))
      (node (ref "C117") (pin "2") (pinfunction "2_2") (pintype "passive"))
      (node (ref "C118") (pin "2") (pinfunction "2_2") (pintype "passive"))
      (node (ref "C119") (pin "2") (pinfunction "2_2") (pintype "passive"))
      (node (ref "C120") (pin "2") (pinfunction "2_2") (pintype "passive"))
      (node (ref "C121") (pin "2") (pinfunction "2_2") (pintype "passive"))
      (node (ref "C122") (pin "2") (pinfunction "2_2") (pintype "passive"))
      (node (ref "C123") (pin "2") (pinfunction "2_2") (pintype "passive"))
      (node (ref "C124") (pin "2") (pinfunction "2_2") (pintype "passive"))
      (node (ref "C125") (pin "2") (pinfunction "2_2") (pintype "passive"))
      (node (ref "C126") (pin "2") (pinfunction "2_2") (pintype "passive"))
      (node (ref "C127") (pin "2") (pinfunction "2_2") (pintype "passive"))
      (node (ref "C128") (pin "2") (pinfunction "2_2") (pintype "passive"))
      (node (ref "C129") (pin "2") (pinfunction "2_2") (pintype "passive"))
      (node (ref "C130") (pin "2") (pinfunction "2_2") (pintype "passive"))
      (node (ref "C131") (pin "2") (pinfunction "2_2") (pintype "passive"))
      (node (ref "J16") (pin "1") (pinfunction "1_1") (pintype "passive"))
      (node (ref "R177") (pin "2") (pinfunction "2_2") (pintype "passive"))
      (node (ref "R184") (pin "1") (pinfunction "1_1") (pintype "passive"))
      (node (ref "R192") (pin "2") (pinfunction "2_2") (pintype "passive"))
      (node (ref "R193") (pin "1") (pinfunction "1_1") (pintype "passive"))
      (node (ref "R194") (pin "1") (pinfunction "1_1") (pintype "passive"))
      (node (ref "R196") (pin "1") (pinfunction "1_1") (pintype "passive"))
      (node (ref "R197") (pin "2") (pinfunction "2_2") (pintype "passive"))
      (node (ref "R198") (pin "2") (pinfunction "2_2") (pintype "passive"))
      (node (ref "U21") (pin "105") (pinfunction "VDD_1_105") (pintype "passive"))
      (node (ref "U21") (pin "113") (pinfunction "VDD_1_113") (pintype "passive"))
      (node (ref "U21") (pin "120") (pinfunction "VDD50USB_120") (pintype "passive"))
      (node (ref "U21") (pin "121") (pinfunction "VDD33USB_121") (pintype "passive"))
      (node (ref "U21") (pin "126") (pinfunction "VDD_1_126") (pintype "passive"))
      (node (ref "U21") (pin "13") (pinfunction "VDD_1_13") (pintype "passive"))
      (node (ref "U21") (pin "136") (pinfunction "VDD_1_136") (pintype "passive"))
      (node (ref "U21") (pin "152") (pinfunction "VDD_1_152") (pintype "passive"))
      (node (ref "U21") (pin "160") (pinfunction "VDD_2_160") (pintype "passive"))
      (node (ref "U21") (pin "176") (pinfunction "VDD_2_176") (pintype "passive"))
      (node (ref "U21") (pin "25") (pinfunction "VDD_1_25") (pintype "passive"))
      (node (ref "U21") (pin "40") (pinfunction "VDDA_40") (pintype "passive"))
      (node (ref "U21") (pin "44") (pinfunction "VDD_1_44") (pintype "passive"))
      (node (ref "U21") (pin "48") (pinfunction "VDD_1_48") (pintype "passive"))
      (node (ref "U21") (pin "65") (pinfunction "VDD_1_65") (pintype "passive"))
      (node (ref "U21") (pin "7") (pinfunction "VDD_1_7") (pintype "passive"))
      (node (ref "U21") (pin "71") (pinfunction "VDD_1_71") (pintype "passive"))
      (node (ref "U21") (pin "8") (pinfunction "VBAT_8") (pintype "passive"))
      (node (ref "U21") (pin "84") (pinfunction "VDD_1_84") (pintype "passive"))
      (node (ref "U21") (pin "92") (pinfunction "VDD_1_92") (pintype "passive"))
      (node (ref "U21") (pin "99") (pinfunction "VDD_1_99") (pintype "passive"))
      (node (ref "U22") (pin "1") (pinfunction "V+_1") (pintype "power_in"))
      (node (ref "U23") (pin "8") (pinfunction "VCC_8") (pintype "power_in"))
    )
    (net (code "64") (name "GND") (class "Default")
      (node (ref "C102") (pin "1") (pinfunction "1_1") (pintype "passive"))
      (node (ref "C103") (pin "1") (pinfunction "1_1") (pintype "passive"))
      (node (ref "C104") (pin "1") (pinfunction "1_1") (pintype "passive"))
      (node (ref "C105") (pin "1") (pinfunction "1_1") (pintype "passive"))
      (node (ref "C106") (pin "1") (pinfunction "1_1") (pintype "passive"))
      (node (ref "C107") (pin "1") (pinfunction "1_1") (pintype "passive"))
      (node (ref "C108") (pin "1") (pinfunction "1_1") (pintype "passive"))
      (node (ref "C109") (pin "1") (pinfunction "1_1") (pintype "passive"))
      (node (ref "C110") (pin "1") (pinfunction "1_1") (pintype "passive"))
      (node (ref "C111") (pin "1") (pinfunction "1_1") (pintype "passive"))
      (node (ref "C112") (pin "1") (pinfunction "1_1") (pintype "passive"))
      (node (ref "C113") (pin "1") (pinfunction "1_1") (pintype "passive"))
      (node (ref "C114") (pin "1") (pinfunction "1_1") (pintype "passive"))
      (node (ref "C115") (pin "1") (pinfunction "1_1") (pintype "passive"))
      (node (ref "C116") (pin "1") (pinfunction "1_1") (pintype "passive"))
      (node (ref "C117") (pin "1") (pinfunction "1_1") (pintype "passive"))
      (node (ref "C118") (pin "1") (pinfunction "1_1") (pintype "passive"))
      (node (ref "C119") (pin "1") (pinfunction "1_1") (pintype "passive"))
      (node (ref "C120") (pin "1") (pinfunction "1_1") (pintype "passive"))
      (node (ref "C121") (pin "1") (pinfunction "1_1") (pintype "passive"))
      (node (ref "C122") (pin "1") (pinfunction "1_1") (pintype "passive"))
      (node (ref "C123") (pin "1") (pinfunction "1_1") (pintype "passive"))
      (node (ref "C124") (pin "1") (pinfunction "1_1") (pintype "passive"))
      (node (ref "C125") (pin "1") (pinfunction "1_1") (pintype "passive"))
      (node (ref "C126") (pin "1") (pinfunction "1_1") (pintype "passive"))
      (node (ref "C127") (pin "1") (pinfunction "1_1") (pintype "passive"))
      (node (ref "C128") (pin "1") (pinfunction "1_1") (pintype "passive"))
      (node (ref "C129") (pin "1") (pinfunction "1_1") (pintype "passive"))
      (node (ref "C130") (pin "1") (pinfunction "1_1") (pintype "passive"))
      (node (ref "C131") (pin "1") (pinfunction "1_1") (pintype "passive"))
      (node (ref "J16") (pin "3") (pinfunction "3_3") (pintype "passive"))
      (node (ref "J16") (pin "5") (pinfunction "5_5") (pintype "passive"))
      (node (ref "R178") (pin "2") (pinfunction "2_2") (pintype "passive"))
      (node (ref "R205") (pin "2") (pinfunction "2_2") (pintype "passive"))
      (node (ref "U21") (pin "100") (pinfunction "VSS_1_100") (pintype "passive"))
      (node (ref "U21") (pin "106") (pinfunction "VSS_1_106") (pintype "passive"))
      (node (ref "U21") (pin "112") (pinfunction "VSS_1_112") (pintype "passive"))
      (node (ref "U21") (pin "119") (pinfunction "VSS_1_119") (pintype "passive"))
      (node (ref "U21") (pin "12") (pinfunction "VSS_1_12") (pintype "passive"))
      (node (ref "U21") (pin "134") (pinfunction "VSS_1_134") (pintype "passive"))
      (node (ref "U21") (pin "137") (pinfunction "VSS_2_137") (pintype "passive"))
      (node (ref "U21") (pin "14") (pinfunction "VSSSMPS_14") (pintype "passive"))
      (node (ref "U21") (pin "151") (pinfunction "VSS_2_151") (pintype "passive"))
      (node (ref "U21") (pin "159") (pinfunction "VSS_2_159") (pintype "passive"))
      (node (ref "U21") (pin "173") (pinfunction "VSS_2_173") (pintype "passive"))
      (node (ref "U21") (pin "24") (pinfunction "VSS_1_24") (pintype "passive"))
      (node (ref "U21") (pin "38") (pinfunction "VSSA_38") (pintype "passive"))
      (node (ref "U21") (pin "45") (pinfunction "VSS_1_45") (pintype "passive"))
      (node (ref "U21") (pin "47") (pinfunction "VSS_1_47") (pintype "passive"))
      (node (ref "U21") (pin "6") (pinfunction "VSS_1_6") (pintype "passive"))
      (node (ref "U21") (pin "64") (pinfunction "VSS_1_64") (pintype "passive"))
      (node (ref "U21") (pin "70") (pinfunction "VSS_1_70") (pintype "passive"))
      (node (ref "U21") (pin "81") (pinfunction "VSS_1_81") (pintype "passive"))
      (node (ref "U21") (pin "83") (pinfunction "VSS_1_83") (pintype "passive"))
      (node (ref "U21") (pin "93") (pinfunction "VSS_1_93") (pintype "passive"))
      (node (ref "U22") (pin "2") (pinfunction "GND_2") (pintype "power_in"))
      (node (ref "U22") (pin "4") (pinfunction "DIV_4") (pintype "passive"))
      (node (ref "U23") (pin "4") (pinfunction "VSS_4") (pintype "power_in"))
    )
    (net (code "65") (name "Net-(J16-Pad2)") (class "Default")
      (node (ref "J16") (pin "2") (pinfunction "2_2") (pintype "passive"))
      (node (ref "R173") (pin "2") (pinfunction "2_2") (pintype "passive"))
    )
    (net (code "66") (name "Net-(J16-Pad4)") (class "Default")
      (node (ref "J16") (pin "4") (pinfunction "4_4") (pintype "passive"))
      (node (ref "R174") (pin "2") (pinfunction "2_2") (pintype "passive"))
    )
    (net (code "67") (name "Net-(J16-Pad6)") (class "Default")
      (node (ref "J16") (pin "6") (pinfunction "6_6") (pintype "passive"))
      (node (ref "R175") (pin "2") (pinfunction "2_2") (pintype "passive"))
    )
    (net (code "68") (name "Net-(J16-Pad10)") (class "Default")
      (node (ref "J16") (pin "10") (pinfunction "10_10") (pintype "passive"))
      (node (ref "R176") (pin "2") (pinfunction "2_2") (pintype "passive"))
    )
    (net (code "69") (name "Net-(U21A-PA4)") (class "Default")
      (node (ref "R223") (pin "1") (pinfunction "1_1") (pintype "passive"))
      (node (ref "U21") (pin "49") (pinfunction "PA4_49") (pintype "passive"))
    )
    (net (code "70") (name "Net-(U21A-PA5)") (class "Default")
      (node (ref "R224") (pin "1") (pinfunction "1_1") (pintype "passive"))
      (node (ref "U21") (pin "50") (pinfunction "PA5_50") (pintype "passive"))
    )
    (net (code "71") (name "Net-(U21A-PA6)") (class "Default")
      (node (ref "R225") (pin "1") (pinfunction "1_1") (pintype "passive"))
      (node (ref "U21") (pin "51") (pinfunction "PA6_51") (pintype "passive"))
    )
    (net (code "72") (name "Net-(U21A-PA7)") (class "Default")
      (node (ref "R226") (pin "1") (pinfunction "1_1") (pintype "passive"))
      (node (ref "U21") (pin "52") (pinfunction "PA7_52") (pintype "passive"))
    )
    (net (code "73") (name "Net-(U21A-PB13)") (class "Default")
      (node (ref "R179") (pin "1") (pinfunction "1_1") (pintype "passive"))
      (node (ref "U21") (pin "86") (pinfunction "PB13_86") (pintype "passive"))
    )
    (net (code "74") (name "Net-(U21A-PC2_C)") (class "Default")
      (node (ref "R182") (pin "1") (pinfunction "1_1") (pintype "passive"))
      (node (ref "U21") (pin "36") (pinfunction "PC2_C_36") (pintype "passive"))
    )
    (net (code "75") (name "Net-(U21A-PC3_C)") (class "Default")
      (node (ref "R185") (pin "1") (pinfunction "1_1") (pintype "passive"))
      (node (ref "U21") (pin "37") (pinfunction "PC3_C_37") (pintype "passive"))
    )
    (net (code "76") (name "Net-(U21B-BOOT0)") (class "Default")
      (node (ref "R177") (pin "1") (pinfunction "1_1") (pintype "passive"))
      (node (ref "R178") (pin "1") (pinfunction "1_1") (pintype "passive"))
      (node (ref "U21") (pin "167") (pinfunction "BOOT0_167") (pintype "passive"))
    )
    (net (code "77") (name "Net-(U21B-PDR_ON)") (class "Default")
      (node (ref "R184") (pin "2") (pinfunction "2_2") (pintype "passive"))
      (node (ref "U21") (pin "174") (pinfunction "PDR_ON_174") (pintype "passive"))
    )
    (net (code "78") (name "Net-(U21B-PK0)") (class "Default")
      (node (ref "R220") (pin "2") (pinfunction "2_2") (pintype "passive"))
      (node (ref "U21") (pin "107") (pinfunction "PK0_107") (pintype "passive"))
    )
    (net (code "79") (name "Net-(U21B-PK1)") (class "Default")
      (node (ref "R221") (pin "2") (pinfunction "2_2") (pintype "passive"))
      (node (ref "U21") (pin "108") (pinfunction "PK1_108") (pintype "passive"))
    )
    (net (code "80") (name "Net-(U21B-PK2)") (class "Default")
      (node (ref "R222") (pin "2") (pinfunction "2_2") (pintype "passive"))
      (node (ref "U21") (pin "109") (pinfunction "PK2_109") (pintype "passive"))
    )
    (net (code "81") (name "Net-(U22-SET)") (class "Default")
      (node (ref "R196") (pin "2") (pinfunction "2_2") (pintype "passive"))
      (node (ref "U22") (pin "3") (pinfunction "SET_3") (pintype "passive"))
    )
    (net (code "82") (name "Net-(U23-~{WC})") (class "Default")
      (node (ref "R204") (pin "1") (pinfunction "1_1") (pintype "passive"))
      (node (ref "R205") (pin "1") (pinfunction "1_1") (pintype "passive"))
      (node (ref "U23") (pin "7") (pinfunction "~{WC}_7") (pintype "passive"))
    )
    (net (code "83") (name "SMPSR") (class "Default")
      (node (ref "C107") (pin "2") (pinfunction "2_2") (pintype "passive"))
      (node (ref "C108") (pin "2") (pinfunction "2_2") (pintype "passive"))
      (node (ref "L4") (pin "2") (pinfunction "2_2") (pintype "passive"))
      (node (ref "R195") (pin "2") (pinfunction "2_2") (pintype "passive"))
      (node (ref "U21") (pin "17") (pinfunction "VFBSMPS_17") (pintype "passive"))
    )
    (net (code "84") (name "VCAP") (class "Default")
      (node (ref "C109") (pin "2") (pinfunction "2_2") (pintype "passive"))
      (node (ref "C110") (pin "2") (pinfunction "2_2") (pintype "passive"))
      (node (ref "C111") (pin "2") (pinfunction "2_2") (pintype "passive"))
      (node (ref "U21") (pin "133") (pinfunction "VCAP_133") (pintype "passive"))
      (node (ref "U21") (pin "172") (pinfunction "VCAP_172") (pintype "passive"))
      (node (ref "U21") (pin "80") (pinfunction "VCAP_80") (pintype "passive"))
    )
    (net (code "85") (name "VDDLDO") (class "Default")
      (node (ref "C104") (pin "2") (pinfunction "2_2") (pintype "passive"))
      (node (ref "C105") (pin "2") (pinfunction "2_2") (pintype "passive"))
      (node (ref "C106") (pin "2") (pinfunction "2_2") (pintype "passive"))
      (node (ref "R192") (pin "1") (pinfunction "1_1") (pintype "passive"))
      (node (ref "R195") (pin "1") (pinfunction "1_1") (pintype "passive"))
      (node (ref "U21") (pin "135") (pinfunction "VDDLDO_135") (pintype "passive"))
      (node (ref "U21") (pin "175") (pinfunction "VDDLDO_175") (pintype "passive"))
      (node (ref "U21") (pin "82") (pinfunction "VDDLDO_82") (pintype "passive"))
    )
    (net (code "86") (name "VDDSMPS") (class "Default")
      (node (ref "R198") (pin "1") (pinfunction "1_1") (pintype "passive"))
      (node (ref "U21") (pin "16") (pinfunction "VDDSMPS_16") (pintype "passive"))
    )
    (net (code "87") (name "VREF") (class "Default")
      (node (ref "R197") (pin "1") (pinfunction "1_1") (pintype "passive"))
      (node (ref "U21") (pin "39") (pinfunction "VREF+_39") (pintype "passive"))
    )
    (net (code "88") (name "unconnected-(J16-Pad7)") (class "Default")
      (node (ref "J16") (pin "7") (pinfunction "7_7") (pintype "passive+no_connect"))
    )
    (net (code "89") (name "unconnected-(J16-Pad8)") (class "Default")
      (node (ref "J16") (pin "8") (pinfunction "8_8") (pintype "passive+no_connect"))
    )
    (net (code "90") (name "unconnected-(J16-Pad9)") (class "Default")
      (node (ref "J16") (pin "9") (pinfunction "9_9") (pintype "passive+no_connect"))
    )
    (net (code "91") (name "unconnected-(R220-Pad1)") (class "Default")
      (node (ref "R220") (pin "1") (pinfunction "1_1") (pintype "passive+no_connect"))
    )
    (net (code "92") (name "unconnected-(R221-Pad1)") (class "Default")
      (node (ref "R221") (pin "1") (pinfunction "1_1") (pintype "passive+no_connect"))
    )
    (net (code "93") (name "unconnected-(R222-Pad1)") (class "Default")
      (node (ref "R222") (pin "1") (pinfunction "1_1") (pintype "passive+no_connect"))
    )
    (net (code "94") (name "unconnected-(R223-Pad2)") (class "Default")
      (node (ref "R223") (pin "2") (pinfunction "2_2") (pintype "passive+no_connect"))
    )
    (net (code "95") (name "unconnected-(R224-Pad2)") (class "Default")
      (node (ref "R224") (pin "2") (pinfunction "2_2") (pintype "passive+no_connect"))
    )
    (net (code "96") (name "unconnected-(R225-Pad2)") (class "Default")
      (node (ref "R225") (pin "2") (pinfunction "2_2") (pintype "passive+no_connect"))
    )
    (net (code "97") (name "unconnected-(R226-Pad2)") (class "Default")
      (node (ref "R226") (pin "2") (pinfunction "2_2") (pintype "passive+no_connect"))
    )
    (net (code "98") (name "unconnected-(U21A-PA2-Pad43)") (class "Default")
      (node (ref "U21") (pin "43") (pinfunction "PA2_43") (pintype "passive"))
    )
    (net (code "99") (name "unconnected-(U21A-PA3-Pad46)") (class "Default")
      (node (ref "U21") (pin "46") (pinfunction "PA3_46") (pintype "passive"))
    )
    (net (code "100") (name "unconnected-(U21A-PA8-Pad127)") (class "Default")
      (node (ref "U21") (pin "127") (pinfunction "PA8_127") (pintype "passive"))
    )
    (net (code "101") (name "unconnected-(U21A-PA11-Pad130)") (class "Default")
      (node (ref "U21") (pin "130") (pinfunction "PA11_130") (pintype "passive"))
    )
    (net (code "102") (name "unconnected-(U21A-PA12-Pad131)") (class "Default")
      (node (ref "U21") (pin "131") (pinfunction "PA12_131") (pintype "passive"))
    )
    (net (code "103") (name "unconnected-(U21A-PA15-Pad139)") (class "Default")
      (node (ref "U21") (pin "139") (pinfunction "PA15_139") (pintype "passive"))
    )
    (net (code "104") (name "unconnected-(U21A-PB0-Pad55)") (class "Default")
      (node (ref "U21") (pin "55") (pinfunction "PB0_55") (pintype "passive"))
    )
    (net (code "105") (name "unconnected-(U21A-PB1-Pad56)") (class "Default")
      (node (ref "U21") (pin "56") (pinfunction "PB1_56") (pintype "passive"))
    )
    (net (code "106") (name "unconnected-(U21A-PB2-Pad57)") (class "Default")
      (node (ref "U21") (pin "57") (pinfunction "PB2_57") (pintype "passive"))
    )
    (net (code "107") (name "unconnected-(U21A-PB4-Pad163)") (class "Default")
      (node (ref "U21") (pin "163") (pinfunction "PB4_163") (pintype "passive"))
    )
    (net (code "108") (name "unconnected-(U21A-PB5-Pad164)") (class "Default")
      (node (ref "U21") (pin "164") (pinfunction "PB5_164") (pintype "passive"))
    )
    (net (code "109") (name "unconnected-(U21A-PB6-Pad165)") (class "Default")
      (node (ref "U21") (pin "165") (pinfunction "PB6_165") (pintype "passive"))
    )
    (net (code "110") (name "unconnected-(U21A-PB9-Pad169)") (class "Default")
      (node (ref "U21") (pin "169") (pinfunction "PB9_169") (pintype "passive"))
    )
    (net (code "111") (name "unconnected-(U21A-PB10-Pad78)") (class "Default")
      (node (ref "U21") (pin "78") (pinfunction "PB10_78") (pintype "passive"))
    )
    (net (code "112") (name "unconnected-(U21A-PB11-Pad79)") (class "Default")
      (node (ref "U21") (pin "79") (pinfunction "PB11_79") (pintype "passive"))
    )
    (net (code "113") (name "unconnected-(U21A-PB12-Pad85)") (class "Default")
      (node (ref "U21") (pin "85") (pinfunction "PB12_85") (pintype "passive"))
    )
    (net (code "114") (name "unconnected-(U21A-PB14-Pad87)") (class "Default")
      (node (ref "U21") (pin "87") (pinfunction "PB14_87") (pintype "passive"))
    )
    (net (code "115") (name "unconnected-(U21A-PB15-Pad88)") (class "Default")
      (node (ref "U21") (pin "88") (pinfunction "PB15_88") (pintype "passive"))
    )
    (net (code "116") (name "unconnected-(U21A-PC0-Pad34)") (class "Default")
      (node (ref "U21") (pin "34") (pinfunction "PC0_34") (pintype "passive"))
    )
    (net (code "117") (name "unconnected-(U21A-PC1-Pad35)") (class "Default")
      (node (ref "U21") (pin "35") (pinfunction "PC1_35") (pintype "passive"))
    )
    (net (code "118") (name "unconnected-(U21A-PC4-Pad53)") (class "Default")
      (node (ref "U21") (pin "53") (pinfunction "PC4_53") (pintype "passive"))
    )
    (net (code "119") (name "unconnected-(U21A-PC5-Pad54)") (class "Default")
      (node (ref "U21") (pin "54") (pinfunction "PC5_54") (pintype "passive"))
    )
    (net (code "120") (name "unconnected-(U21A-PC6-Pad122)") (class "Default")
      (node (ref "U21") (pin "122") (pinfunction "PC6_122") (pintype "passive"))
    )
    (net (code "121") (name "unconnected-(U21A-PC7-Pad123)") (class "Default")
      (node (ref "U21") (pin "123") (pinfunction "PC7_123") (pintype "passive"))
    )
    (net (code "122") (name "unconnected-(U21A-PC8-Pad124)") (class "Default")
      (node (ref "U21") (pin "124") (pinfunction "PC8_124") (pintype "passive"))
    )
    (net (code "123") (name "unconnected-(U21A-PC9-Pad125)") (class "Default")
      (node (ref "U21") (pin "125") (pinfunction "PC9_125") (pintype "passive"))
    )
    (net (code "124") (name "unconnected-(U21A-PC10-Pad140)") (class "Default")
      (node (ref "U21") (pin "140") (pinfunction "PC10_140") (pintype "passive"))
    )
    (net (code "125") (name "unconnected-(U21A-PC11-Pad141)") (class "Default")
      (node (ref "U21") (pin "141") (pinfunction "PC11_141") (pintype "passive"))
    )
    (net (code "126") (name "unconnected-(U21A-PC12-Pad142)") (class "Default")
      (node (ref "U21") (pin "142") (pinfunction "PC12_142") (pintype "passive"))
    )
    (net (code "127") (name "unconnected-(U21A-PC13-Pad9)") (class "Default")
      (node (ref "U21") (pin "9") (pinfunction "PC13_9") (pintype "passive"))
    )
    (net (code "128") (name "unconnected-(U21A-PC14-OSC32_IN-Pad10)") (class "Default")
      (node (ref "U21") (pin "10") (pinfunction "PC14-OSC32_IN_10") (pintype "passive"))
    )
    (net (code "129") (name "unconnected-(U21A-PC15-OSC32_OUT-Pad11)") (class "Default")
      (node (ref "U21") (pin "11") (pinfunction "PC15-OSC32_OUT_11") (pintype "passive"))
    )
    (net (code "130") (name "unconnected-(U21A-PE12-Pad74)") (class "Default")
      (node (ref "U21") (pin "74") (pinfunction "PE12_74") (pintype "passive"))
    )
    (net (code "131") (name "unconnected-(U21A-PE13-Pad75)") (class "Default")
      (node (ref "U21") (pin "75") (pinfunction "PE13_75") (pintype "passive"))
    )
    (net (code "132") (name "unconnected-(U21A-PE14-Pad76)") (class "Default")
      (node (ref "U21") (pin "76") (pinfunction "PE14_76") (pintype "passive"))
    )
    (net (code "133") (name "unconnected-(U21A-PE15-Pad77)") (class "Default")
      (node (ref "U21") (pin "77") (pinfunction "PE15_77") (pintype "passive"))
    )
    (net (code "134") (name "unconnected-(U21A-PF8-Pad28)") (class "Default")
      (node (ref "U21") (pin "28") (pinfunction "PF8_28") (pintype "passive"))
    )
    (net (code "135") (name "unconnected-(U21A-PF9-Pad29)") (class "Default")
      (node (ref "U21") (pin "29") (pinfunction "PF9_29") (pintype "passive"))
    )
    (net (code "136") (name "unconnected-(U21A-PF10-Pad30)") (class "Default")
      (node (ref "U21") (pin "30") (pinfunction "PF10_30") (pintype "passive"))
    )
    (net (code "137") (name "unconnected-(U21A-PF11-Pad58)") (class "Default")
      (node (ref "U21") (pin "58") (pinfunction "PF11_58") (pintype "passive"))
    )
    (net (code "138") (name "unconnected-(U21A-PF12-Pad59)") (class "Default")
      (node (ref "U21") (pin "59") (pinfunction "PF12_59") (pintype "passive"))
    )
    (net (code "139") (name "unconnected-(U21A-PF13-Pad60)") (class "Default")
      (node (ref "U21") (pin "60") (pinfunction "PF13_60") (pintype "passive"))
    )
    (net (code "140") (name "unconnected-(U21A-PF14-Pad61)") (class "Default")
      (node (ref "U21") (pin "61") (pinfunction "PF14_61") (pintype "passive"))
    )
    (net (code "141") (name "unconnected-(U21A-PF15-Pad62)") (class "Default")
      (node (ref "U21") (pin "62") (pinfunction "PF15_62") (pintype "passive"))
    )
    (net (code "142") (name "unconnected-(U21B-PG0-Pad63)") (class "Default")
      (node (ref "U21") (pin "63") (pinfunction "PG0_63") (pintype "passive"))
    )
    (net (code "143") (name "unconnected-(U21B-PG1-Pad66)") (class "Default")
      (node (ref "U21") (pin "66") (pinfunction "PG1_66") (pintype "passive"))
    )
    (net (code "144") (name "unconnected-(U21B-PG2-Pad110)") (class "Default")
      (node (ref "U21") (pin "110") (pinfunction "PG2_110") (pintype "passive"))
    )
    (net (code "145") (name "unconnected-(U21B-PG3-Pad111)") (class "Default")
      (node (ref "U21") (pin "111") (pinfunction "PG3_111") (pintype "passive"))
    )
    (net (code "146") (name "unconnected-(U21B-PG4-Pad114)") (class "Default")
      (node (ref "U21") (pin "114") (pinfunction "PG4_114") (pintype "passive"))
    )
    (net (code "147") (name "unconnected-(U21B-PG5-Pad115)") (class "Default")
      (node (ref "U21") (pin "115") (pinfunction "PG5_115") (pintype "passive"))
    )
    (net (code "148") (name "unconnected-(U21B-PG6-Pad116)") (class "Default")
      (node (ref "U21") (pin "116") (pinfunction "PG6_116") (pintype "passive"))
    )
    (net (code "149") (name "unconnected-(U21B-PG7-Pad117)") (class "Default")
      (node (ref "U21") (pin "117") (pinfunction "PG7_117") (pintype "passive"))
    )
    (net (code "150") (name "unconnected-(U21B-PG8-Pad118)") (class "Default")
      (node (ref "U21") (pin "118") (pinfunction "PG8_118") (pintype "passive"))
    )
    (net (code "151") (name "unconnected-(U21B-PG9-Pad153)") (class "Default")
      (node (ref "U21") (pin "153") (pinfunction "PG9_153") (pintype "passive"))
    )
    (net (code "152") (name "unconnected-(U21B-PG10-Pad154)") (class "Default")
      (node (ref "U21") (pin "154") (pinfunction "PG10_154") (pintype "passive"))
    )
    (net (code "153") (name "unconnected-(U21B-PG11-Pad155)") (class "Default")
      (node (ref "U21") (pin "155") (pinfunction "PG11_155") (pintype "passive"))
    )
    (net (code "154") (name "unconnected-(U21B-PG12-Pad156)") (class "Default")
      (node (ref "U21") (pin "156") (pinfunction "PG12_156") (pintype "passive"))
    )
    (net (code "155") (name "unconnected-(U21B-PG13-Pad157)") (class "Default")
      (node (ref "U21") (pin "157") (pinfunction "PG13_157") (pintype "passive"))
    )
    (net (code "156") (name "unconnected-(U21B-PG14-Pad158)") (class "Default")
      (node (ref "U21") (pin "158") (pinfunction "PG14_158") (pintype "passive"))
    )
    (net (code "157") (name "unconnected-(U21B-PG15-Pad161)") (class "Default")
      (node (ref "U21") (pin "161") (pinfunction "PG15_161") (pintype "passive"))
    )
    (net (code "158") (name "unconnected-(U21B-PH1-OSC_OUT-Pad32)") (class "Default")
      (node (ref "U21") (pin "32") (pinfunction "PH1-OSC_OUT_32") (pintype "passive"))
    )
    (net (code "159") (name "unconnected-(U21B-PJ8-Pad101)") (class "Default")
      (node (ref "U21") (pin "101") (pinfunction "PJ8_101") (pintype "passive"))
    )
    (net (code "160") (name "unconnected-(U21B-PJ9-Pad102)") (class "Default")
      (node (ref "U21") (pin "102") (pinfunction "PJ9_102") (pintype "passive"))
    )
    (net (code "161") (name "unconnected-(U21B-PJ10-Pad103)") (class "Default")
      (node (ref "U21") (pin "103") (pinfunction "PJ10_103") (pintype "passive"))
    )
    (net (code "162") (name "unconnected-(U21B-PJ11-Pad104)") (class "Default")
      (node (ref "U21") (pin "104") (pinfunction "PJ11_104") (pintype "passive"))
    )
    (net (code "163") (name "unconnected-(U23-NC-Pad1)") (class "Default")
      (node (ref "U23") (pin "1") (pinfunction "NC_1") (pintype "passive"))
    )
    (net (code "164") (name "unconnected-(U23-NC-Pad2)") (class "Default")
      (node (ref "U23") (pin "2") (pinfunction "NC_2") (pintype "passive"))
    )
    (net (code "165") (name "unconnected-(U23-NC-Pad3)") (class "Default")
      (node (ref "U23") (pin "3") (pinfunction "NC_3") (pintype "passive"))
    )
  )
)
